# SH2-CONTROLS.net
KiCad netlist of a schematic drawn in Altium Designer
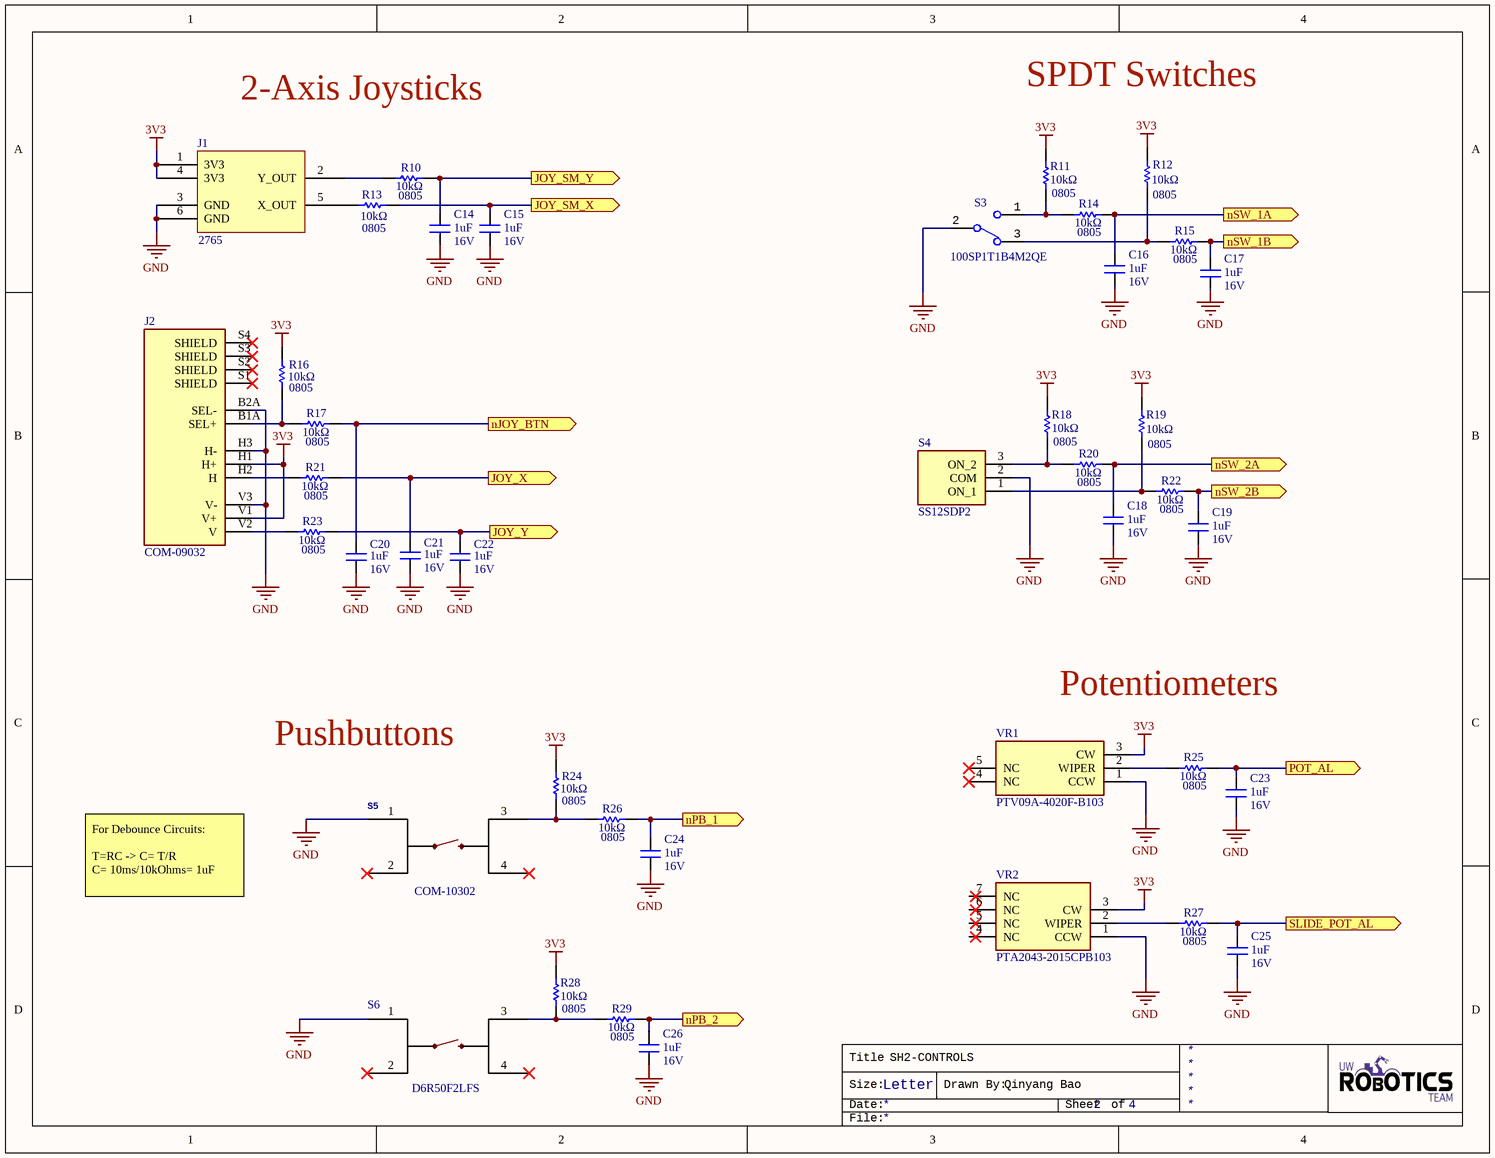
[diagram p0: SH2-CONTROLS.SchDoc]

(export (version "E")
  (design (tool "Eeschema 10.0.6"))
  (components
    (comp (ref "C14")
      (value "1uF")
      (footprint "CAPC2012X140N")
      (description "CAP CER 1UF 16V X7R 0805")
      (fields
        (field (name "TOLERANCE") "10%")
        (field (name "VOLTAGE RATING") "16V")
        (field (name "Comment") "CAP_1uF_16V_0805")
      )
      (libsource (lib "UWRT_Schematic_Library_2020") (part "CAP_1uF_16V_0805"))
    )
    (comp (ref "C15")
      (value "1uF")
      (footprint "CAPC2012X140N")
      (description "CAP CER 1UF 16V X7R 0805")
      (fields
        (field (name "TOLERANCE") "10%")
        (field (name "VOLTAGE RATING") "16V")
        (field (name "Comment") "CAP_1uF_16V_0805")
      )
      (libsource (lib "UWRT_Schematic_Library_2020") (part "CAP_1uF_16V_0805"))
    )
    (comp (ref "C16")
      (value "1uF")
      (footprint "CAPC2012X140N")
      (description "CAP CER 1UF 16V X7R 0805")
      (fields
        (field (name "TOLERANCE") "10%")
        (field (name "VOLTAGE RATING") "16V")
        (field (name "Comment") "CAP_1uF_16V_0805")
      )
      (libsource (lib "UWRT_Schematic_Library_2020") (part "CAP_1uF_16V_0805"))
    )
    (comp (ref "C17")
      (value "1uF")
      (footprint "CAPC2012X140N")
      (description "CAP CER 1UF 16V X7R 0805")
      (fields
        (field (name "TOLERANCE") "10%")
        (field (name "VOLTAGE RATING") "16V")
        (field (name "Comment") "CAP_1uF_16V_0805")
      )
      (libsource (lib "UWRT_Schematic_Library_2020") (part "CAP_1uF_16V_0805"))
    )
    (comp (ref "C18")
      (value "1uF")
      (footprint "CAPC2012X140N")
      (description "CAP CER 1UF 16V X7R 0805")
      (fields
        (field (name "TOLERANCE") "10%")
        (field (name "VOLTAGE RATING") "16V")
        (field (name "Comment") "CAP_1uF_16V_0805")
      )
      (libsource (lib "UWRT_Schematic_Library_2020") (part "CAP_1uF_16V_0805"))
    )
    (comp (ref "C19")
      (value "1uF")
      (footprint "CAPC2012X140N")
      (description "CAP CER 1UF 16V X7R 0805")
      (fields
        (field (name "TOLERANCE") "10%")
        (field (name "VOLTAGE RATING") "16V")
        (field (name "Comment") "CAP_1uF_16V_0805")
      )
      (libsource (lib "UWRT_Schematic_Library_2020") (part "CAP_1uF_16V_0805"))
    )
    (comp (ref "C20")
      (value "1uF")
      (footprint "CAPC2012X140N")
      (description "CAP CER 1UF 16V X7R 0805")
      (fields
        (field (name "TOLERANCE") "10%")
        (field (name "VOLTAGE RATING") "16V")
        (field (name "Comment") "CAP_1uF_16V_0805")
      )
      (libsource (lib "UWRT_Schematic_Library_2020") (part "CAP_1uF_16V_0805"))
    )
    (comp (ref "C21")
      (value "1uF")
      (footprint "CAPC2012X140N")
      (description "CAP CER 1UF 16V X7R 0805")
      (fields
        (field (name "TOLERANCE") "10%")
        (field (name "VOLTAGE RATING") "16V")
        (field (name "Comment") "CAP_1uF_16V_0805")
      )
      (libsource (lib "UWRT_Schematic_Library_2020") (part "CAP_1uF_16V_0805"))
    )
    (comp (ref "C22")
      (value "1uF")
      (footprint "CAPC2012X140N")
      (description "CAP CER 1UF 16V X7R 0805")
      (fields
        (field (name "TOLERANCE") "10%")
        (field (name "VOLTAGE RATING") "16V")
        (field (name "Comment") "CAP_1uF_16V_0805")
      )
      (libsource (lib "UWRT_Schematic_Library_2020") (part "CAP_1uF_16V_0805"))
    )
    (comp (ref "C23")
      (value "1uF")
      (footprint "CAPC2012X140N")
      (description "CAP CER 1UF 16V X7R 0805")
      (fields
        (field (name "TOLERANCE") "10%")
        (field (name "VOLTAGE RATING") "16V")
        (field (name "Comment") "CAP_1uF_16V_0805")
      )
      (libsource (lib "UWRT_Schematic_Library_2020") (part "CAP_1uF_16V_0805"))
    )
    (comp (ref "C24")
      (value "1uF")
      (footprint "CAPC2012X140N")
      (description "CAP CER 1UF 16V X7R 0805")
      (fields
        (field (name "TOLERANCE") "10%")
        (field (name "VOLTAGE RATING") "16V")
        (field (name "Comment") "CAP_1uF_16V_0805")
      )
      (libsource (lib "UWRT_Schematic_Library_2020") (part "CAP_1uF_16V_0805"))
    )
    (comp (ref "C25")
      (value "1uF")
      (footprint "CAPC2012X140N")
      (description "CAP CER 1UF 16V X7R 0805")
      (fields
        (field (name "TOLERANCE") "10%")
        (field (name "VOLTAGE RATING") "16V")
        (field (name "Comment") "CAP_1uF_16V_0805")
      )
      (libsource (lib "UWRT_Schematic_Library_2020") (part "CAP_1uF_16V_0805"))
    )
    (comp (ref "C26")
      (value "1uF")
      (footprint "CAPC2012X140N")
      (description "CAP CER 1UF 16V X7R 0805")
      (fields
        (field (name "TOLERANCE") "10%")
        (field (name "VOLTAGE RATING") "16V")
        (field (name "Comment") "CAP_1uF_16V_0805")
      )
      (libsource (lib "UWRT_Schematic_Library_2020") (part "CAP_1uF_16V_0805"))
    )
    (comp (ref "J1")
      (value "2_AXIS_JOYSTICK_SMALL")
      (footprint "2_AXIS_JOY_SMALL")
      (description "JOYSTICK 10K OHM 2 AXIS TH")
      (fields (field (name "MANUFACTURER PART NUMBER 1") "2765"))
      (libsource (lib "UWRT_Schematic_Library_2020") (part "2_AXIS_JOYSTICK_SMALL"))
    )
    (comp (ref "J2")
      (value "2_AXIS_JOYSTICK")
      (footprint "2_AXIS_JOY")
      (description "JOYSTICK 10K OHM 2 AXIS TH")
      (fields (field (name "MANUFACTURER PART NUMBER 1") "COM-09032"))
      (libsource (lib "UWRT_Schematic_Library_2020") (part "2_AXIS_JOYSTICK"))
    )
    (comp (ref "R10")
      (value "10kΩ")
      (footprint "RESC2012X60N")
      (description "RES SMD 10K OHM 1% 1/8W 0805")
      (fields
        (field (name "CASE CODE (IMPERIAL)") "0805")
        (field (name "TOLERANCE") "1%")
        (field (name "Comment") "RES_10kΩ_0805")
      )
      (libsource (lib "UWRT_Schematic_Library_2020") (part "RES_10kΩ_0805"))
    )
    (comp (ref "R11")
      (value "10kΩ")
      (footprint "RESC2012X60N")
      (description "RES SMD 10K OHM 1% 1/8W 0805")
      (fields
        (field (name "TOLERANCE") "1%")
        (field (name "CASE CODE (IMPERIAL)") "0805")
        (field (name "Comment") "RES_10kΩ_0805")
      )
      (libsource (lib "UWRT_Schematic_Library_2020") (part "RES_10kΩ_0805"))
    )
    (comp (ref "R12")
      (value "10kΩ")
      (footprint "RESC2012X60N")
      (description "RES SMD 10K OHM 1% 1/8W 0805")
      (fields
        (field (name "TOLERANCE") "1%")
        (field (name "CASE CODE (IMPERIAL)") "0805")
        (field (name "Comment") "RES_10kΩ_0805")
      )
      (libsource (lib "UWRT_Schematic_Library_2020") (part "RES_10kΩ_0805"))
    )
    (comp (ref "R13")
      (value "10kΩ")
      (footprint "RESC2012X60N")
      (description "RES SMD 10K OHM 1% 1/8W 0805")
      (fields
        (field (name "CASE CODE (IMPERIAL)") "0805")
        (field (name "TOLERANCE") "1%")
        (field (name "Comment") "RES_10kΩ_0805")
      )
      (libsource (lib "UWRT_Schematic_Library_2020") (part "RES_10kΩ_0805"))
    )
    (comp (ref "R14")
      (value "10kΩ")
      (footprint "RESC2012X60N")
      (description "RES SMD 10K OHM 1% 1/8W 0805")
      (fields
        (field (name "CASE CODE (IMPERIAL)") "0805")
        (field (name "TOLERANCE") "1%")
        (field (name "Comment") "RES_10kΩ_0805")
      )
      (libsource (lib "UWRT_Schematic_Library_2020") (part "RES_10kΩ_0805"))
    )
    (comp (ref "R15")
      (value "10kΩ")
      (footprint "RESC2012X60N")
      (description "RES SMD 10K OHM 1% 1/8W 0805")
      (fields
        (field (name "CASE CODE (IMPERIAL)") "0805")
        (field (name "TOLERANCE") "1%")
        (field (name "Comment") "RES_10kΩ_0805")
      )
      (libsource (lib "UWRT_Schematic_Library_2020") (part "RES_10kΩ_0805"))
    )
    (comp (ref "R16")
      (value "10kΩ")
      (footprint "RESC2012X60N")
      (description "RES SMD 10K OHM 1% 1/8W 0805")
      (fields
        (field (name "TOLERANCE") "1%")
        (field (name "CASE CODE (IMPERIAL)") "0805")
        (field (name "Comment") "RES_10kΩ_0805")
      )
      (libsource (lib "UWRT_Schematic_Library_2020") (part "RES_10kΩ_0805"))
    )
    (comp (ref "R17")
      (value "10kΩ")
      (footprint "RESC2012X60N")
      (description "RES SMD 10K OHM 1% 1/8W 0805")
      (fields
        (field (name "CASE CODE (IMPERIAL)") "0805")
        (field (name "TOLERANCE") "1%")
        (field (name "Comment") "RES_10kΩ_0805")
      )
      (libsource (lib "UWRT_Schematic_Library_2020") (part "RES_10kΩ_0805"))
    )
    (comp (ref "R18")
      (value "10kΩ")
      (footprint "RESC2012X60N")
      (description "RES SMD 10K OHM 1% 1/8W 0805")
      (fields
        (field (name "TOLERANCE") "1%")
        (field (name "CASE CODE (IMPERIAL)") "0805")
        (field (name "Comment") "RES_10kΩ_0805")
      )
      (libsource (lib "UWRT_Schematic_Library_2020") (part "RES_10kΩ_0805"))
    )
    (comp (ref "R19")
      (value "10kΩ")
      (footprint "RESC2012X60N")
      (description "RES SMD 10K OHM 1% 1/8W 0805")
      (fields
        (field (name "TOLERANCE") "1%")
        (field (name "CASE CODE (IMPERIAL)") "0805")
        (field (name "Comment") "RES_10kΩ_0805")
      )
      (libsource (lib "UWRT_Schematic_Library_2020") (part "RES_10kΩ_0805"))
    )
    (comp (ref "R20")
      (value "10kΩ")
      (footprint "RESC2012X60N")
      (description "RES SMD 10K OHM 1% 1/8W 0805")
      (fields
        (field (name "CASE CODE (IMPERIAL)") "0805")
        (field (name "TOLERANCE") "1%")
        (field (name "Comment") "RES_10kΩ_0805")
      )
      (libsource (lib "UWRT_Schematic_Library_2020") (part "RES_10kΩ_0805"))
    )
    (comp (ref "R21")
      (value "10kΩ")
      (footprint "RESC2012X60N")
      (description "RES SMD 10K OHM 1% 1/8W 0805")
      (fields
        (field (name "CASE CODE (IMPERIAL)") "0805")
        (field (name "TOLERANCE") "1%")
        (field (name "Comment") "RES_10kΩ_0805")
      )
      (libsource (lib "UWRT_Schematic_Library_2020") (part "RES_10kΩ_0805"))
    )
    (comp (ref "R22")
      (value "10kΩ")
      (footprint "RESC2012X60N")
      (description "RES SMD 10K OHM 1% 1/8W 0805")
      (fields
        (field (name "CASE CODE (IMPERIAL)") "0805")
        (field (name "TOLERANCE") "1%")
        (field (name "Comment") "RES_10kΩ_0805")
      )
      (libsource (lib "UWRT_Schematic_Library_2020") (part "RES_10kΩ_0805"))
    )
    (comp (ref "R23")
      (value "10kΩ")
      (footprint "RESC2012X60N")
      (description "RES SMD 10K OHM 1% 1/8W 0805")
      (fields
        (field (name "CASE CODE (IMPERIAL)") "0805")
        (field (name "TOLERANCE") "1%")
        (field (name "Comment") "RES_10kΩ_0805")
      )
      (libsource (lib "UWRT_Schematic_Library_2020") (part "RES_10kΩ_0805"))
    )
    (comp (ref "R24")
      (value "10kΩ")
      (footprint "RESC2012X60N")
      (description "RES SMD 10K OHM 1% 1/8W 0805")
      (fields
        (field (name "TOLERANCE") "1%")
        (field (name "CASE CODE (IMPERIAL)") "0805")
        (field (name "Comment") "RES_10kΩ_0805")
      )
      (libsource (lib "UWRT_Schematic_Library_2020") (part "RES_10kΩ_0805"))
    )
    (comp (ref "R25")
      (value "10kΩ")
      (footprint "RESC2012X60N")
      (description "RES SMD 10K OHM 1% 1/8W 0805")
      (fields
        (field (name "CASE CODE (IMPERIAL)") "0805")
        (field (name "TOLERANCE") "1%")
        (field (name "Comment") "RES_10kΩ_0805")
      )
      (libsource (lib "UWRT_Schematic_Library_2020") (part "RES_10kΩ_0805"))
    )
    (comp (ref "R26")
      (value "10kΩ")
      (footprint "RESC2012X60N")
      (description "RES SMD 10K OHM 1% 1/8W 0805")
      (fields
        (field (name "CASE CODE (IMPERIAL)") "0805")
        (field (name "TOLERANCE") "1%")
        (field (name "Comment") "RES_10kΩ_0805")
      )
      (libsource (lib "UWRT_Schematic_Library_2020") (part "RES_10kΩ_0805"))
    )
    (comp (ref "R27")
      (value "10kΩ")
      (footprint "RESC2012X60N")
      (description "RES SMD 10K OHM 1% 1/8W 0805")
      (fields
        (field (name "CASE CODE (IMPERIAL)") "0805")
        (field (name "TOLERANCE") "1%")
        (field (name "Comment") "RES_10kΩ_0805")
      )
      (libsource (lib "UWRT_Schematic_Library_2020") (part "RES_10kΩ_0805"))
    )
    (comp (ref "R28")
      (value "10kΩ")
      (footprint "RESC2012X60N")
      (description "RES SMD 10K OHM 1% 1/8W 0805")
      (fields
        (field (name "TOLERANCE") "1%")
        (field (name "CASE CODE (IMPERIAL)") "0805")
        (field (name "Comment") "RES_10kΩ_0805")
      )
      (libsource (lib "UWRT_Schematic_Library_2020") (part "RES_10kΩ_0805"))
    )
    (comp (ref "R29")
      (value "10kΩ")
      (footprint "RESC2012X60N")
      (description "RES SMD 10K OHM 1% 1/8W 0805")
      (fields
        (field (name "CASE CODE (IMPERIAL)") "0805")
        (field (name "TOLERANCE") "1%")
        (field (name "Comment") "RES_10kΩ_0805")
      )
      (libsource (lib "UWRT_Schematic_Library_2020") (part "RES_10kΩ_0805"))
    )
    (comp (ref "S3")
      (value "SW_SPDT")
      (footprint "100SP1T1B4M2QE")
      (description "SWITCH TOGGLE SPDT 5A 120V")
      (fields (field (name "MANUFACTURER PART NUMBER 1") "100SP1T1B4M2QE"))
      (libsource (lib "UWRT_Schematic_Library_2020") (part "SW_SPDT"))
    )
    (comp (ref "S4")
      (value "SW_SPDT_SMALL")
      (footprint "SS12SDP2")
      (description "SWITCH SLIDE SPDT 100MA 30V")
      (fields (field (name "MANUFACTURER PART NUMBER 1") "SS12SDP2"))
      (libsource (lib "UWRT_Schematic_Library_2020") (part "SW_SPDT_SMALL"))
    )
    (comp (ref "S5")
      (value "Pushbutton")
      (footprint "TACTILE_SWITCH_PTH_12MM")
      (description "Momentary Switch (Pushbutton) - SPST")
      (fields (field (name "MANUFACTURER PART NUMBER 1") "COM-10302"))
      (libsource (lib "UWRT_Schematic_Library_2020") (part "MOMENTARY_SWITCH_TH"))
    )
    (comp (ref "S6")
      (value "MOMENTARY_SWITCH_D6R")
      (footprint "D6R")
      (description "SWITCH PUSH SPST-NO 0.1A 32V")
      (fields (field (name "MANUFACTURER PART NUMBER 1") "D6R50F2LFS"))
      (libsource (lib "UWRT_Schematic_Library_2020") (part "MOMENTARY_SWITCH_D6R"))
    )
    (comp (ref "VR1")
      (value "POT_10K")
      (footprint "PTV09A4020FB103")
      (description "POT 10K OHM 1/20W CARBON LINEAR")
      (fields
        (field (name "MANUFACTURER PART NUMBER 1") "PTV09A-4020F-B103")
        (field (name "TOLERANCE") "20%")
      )
      (libsource (lib "UWRT_Schematic_Library_2020") (part "POT_10K"))
    )
    (comp (ref "VR2")
      (value "POT_10K_SLIDE")
      (footprint "PTA20432015CPB103")
      (description "SLIDE POT 10K OHM 0.1W TOP 20MM")
      (fields
        (field (name "MANUFACTURER PART NUMBER 1") "PTA2043-2015CPB103")
        (field (name "TOLERANCE") "20%")
      )
      (libsource (lib "UWRT_Schematic_Library_2020") (part "POT_10K_SLIDE"))
    )
  )
  (nets
    (net (code "1") (name "/JOY_SM_X") (class "Default")
      (node (ref "C15") (pin "2") (pinfunction "2_2") (pintype "passive"))
      (node (ref "R13") (pin "2") (pinfunction "2_2") (pintype "passive"))
    )
    (net (code "2") (name "/JOY_SM_Y") (class "Default")
      (node (ref "C14") (pin "2") (pinfunction "2_2") (pintype "passive"))
      (node (ref "R10") (pin "2") (pinfunction "2_2") (pintype "passive"))
    )
    (net (code "3") (name "/JOY_X") (class "Default")
      (node (ref "C21") (pin "2") (pinfunction "2_2") (pintype "passive"))
      (node (ref "R21") (pin "2") (pinfunction "2_2") (pintype "passive"))
    )
    (net (code "4") (name "/JOY_Y") (class "Default")
      (node (ref "C22") (pin "2") (pinfunction "2_2") (pintype "passive"))
      (node (ref "R23") (pin "2") (pinfunction "2_2") (pintype "passive"))
    )
    (net (code "5") (name "/POT_AL") (class "Default")
      (node (ref "C23") (pin "2") (pinfunction "2_2") (pintype "passive"))
      (node (ref "R25") (pin "2") (pinfunction "2_2") (pintype "passive"))
    )
    (net (code "6") (name "/SLIDE_POT_AL") (class "Default")
      (node (ref "C25") (pin "2") (pinfunction "2_2") (pintype "passive"))
      (node (ref "R27") (pin "2") (pinfunction "2_2") (pintype "passive"))
    )
    (net (code "7") (name "/nJOY_BTN") (class "Default")
      (node (ref "C20") (pin "2") (pinfunction "2_2") (pintype "passive"))
      (node (ref "R17") (pin "2") (pinfunction "2_2") (pintype "passive"))
    )
    (net (code "8") (name "/nPB_1") (class "Default")
      (node (ref "C24") (pin "2") (pinfunction "2_2") (pintype "passive"))
      (node (ref "R26") (pin "2") (pinfunction "2_2") (pintype "passive"))
    )
    (net (code "9") (name "/nPB_2") (class "Default")
      (node (ref "C26") (pin "2") (pinfunction "2_2") (pintype "passive"))
      (node (ref "R29") (pin "2") (pinfunction "2_2") (pintype "passive"))
    )
    (net (code "10") (name "/nSW_1A") (class "Default")
      (node (ref "C16") (pin "2") (pinfunction "2_2") (pintype "passive"))
      (node (ref "R14") (pin "2") (pinfunction "2_2") (pintype "passive"))
    )
    (net (code "11") (name "/nSW_1B") (class "Default")
      (node (ref "C17") (pin "2") (pinfunction "2_2") (pintype "passive"))
      (node (ref "R15") (pin "2") (pinfunction "2_2") (pintype "passive"))
    )
    (net (code "12") (name "/nSW_2A") (class "Default")
      (node (ref "C18") (pin "2") (pinfunction "2_2") (pintype "passive"))
      (node (ref "R20") (pin "2") (pinfunction "2_2") (pintype "passive"))
    )
    (net (code "13") (name "/nSW_2B") (class "Default")
      (node (ref "C19") (pin "2") (pinfunction "2_2") (pintype "passive"))
      (node (ref "R22") (pin "2") (pinfunction "2_2") (pintype "passive"))
    )
    (net (code "14") (name "3V3") (class "Default")
      (node (ref "J1") (pin "1") (pinfunction "3V3_1") (pintype "passive"))
      (node (ref "J1") (pin "4") (pinfunction "3V3_4") (pintype "passive"))
      (node (ref "J2") (pin "H1") (pinfunction "H+_H1") (pintype "passive"))
      (node (ref "J2") (pin "V1") (pinfunction "V+_V1") (pintype "passive"))
      (node (ref "R11") (pin "1") (pinfunction "1_1") (pintype "passive"))
      (node (ref "R12") (pin "1") (pinfunction "1_1") (pintype "passive"))
      (node (ref "R16") (pin "1") (pinfunction "1_1") (pintype "passive"))
      (node (ref "R18") (pin "1") (pinfunction "1_1") (pintype "passive"))
      (node (ref "R19") (pin "1") (pinfunction "1_1") (pintype "passive"))
      (node (ref "R24") (pin "1") (pinfunction "1_1") (pintype "passive"))
      (node (ref "R28") (pin "1") (pinfunction "1_1") (pintype "passive"))
      (node (ref "VR1") (pin "3") (pinfunction "CW_3") (pintype "passive"))
      (node (ref "VR2") (pin "3") (pinfunction "CW_3") (pintype "passive"))
    )
    (net (code "15") (name "GND") (class "Default")
      (node (ref "C14") (pin "1") (pinfunction "1_1") (pintype "passive"))
      (node (ref "C15") (pin "1") (pinfunction "1_1") (pintype "passive"))
      (node (ref "C16") (pin "1") (pinfunction "1_1") (pintype "passive"))
      (node (ref "C17") (pin "1") (pinfunction "1_1") (pintype "passive"))
      (node (ref "C18") (pin "1") (pinfunction "1_1") (pintype "passive"))
      (node (ref "C19") (pin "1") (pinfunction "1_1") (pintype "passive"))
      (node (ref "C20") (pin "1") (pinfunction "1_1") (pintype "passive"))
      (node (ref "C21") (pin "1") (pinfunction "1_1") (pintype "passive"))
      (node (ref "C22") (pin "1") (pinfunction "1_1") (pintype "passive"))
      (node (ref "C23") (pin "1") (pinfunction "1_1") (pintype "passive"))
      (node (ref "C24") (pin "1") (pinfunction "1_1") (pintype "passive"))
      (node (ref "C25") (pin "1") (pinfunction "1_1") (pintype "passive"))
      (node (ref "C26") (pin "1") (pinfunction "1_1") (pintype "passive"))
      (node (ref "J1") (pin "3") (pinfunction "GND_3") (pintype "passive"))
      (node (ref "J1") (pin "6") (pinfunction "GND_6") (pintype "passive"))
      (node (ref "J2") (pin "B2A") (pinfunction "SEL-_B2A") (pintype "passive"))
      (node (ref "J2") (pin "H3") (pinfunction "H-_H3") (pintype "passive"))
      (node (ref "J2") (pin "V3") (pinfunction "V-_V3") (pintype "passive"))
      (node (ref "S3") (pin "2") (pinfunction "2_2") (pintype "passive"))
      (node (ref "S4") (pin "2") (pinfunction "COM_2") (pintype "passive"))
      (node (ref "S5") (pin "1") (pinfunction "1_1") (pintype "passive"))
      (node (ref "S6") (pin "1") (pinfunction "1_1") (pintype "passive"))
      (node (ref "VR1") (pin "1") (pinfunction "CCW_1") (pintype "passive"))
      (node (ref "VR2") (pin "1") (pinfunction "CCW_1") (pintype "passive"))
    )
    (net (code "16") (name "Net-(J1-X_OUT)") (class "Default")
      (node (ref "J1") (pin "5") (pinfunction "X_OUT_5") (pintype "passive"))
      (node (ref "R13") (pin "1") (pinfunction "1_1") (pintype "passive"))
    )
    (net (code "17") (name "Net-(J1-Y_OUT)") (class "Default")
      (node (ref "J1") (pin "2") (pinfunction "Y_OUT_2") (pintype "passive"))
      (node (ref "R10") (pin "1") (pinfunction "1_1") (pintype "passive"))
    )
    (net (code "18") (name "Net-(J2-H)") (class "Default")
      (node (ref "J2") (pin "H2") (pinfunction "H_H2") (pintype "passive"))
      (node (ref "R21") (pin "1") (pinfunction "1_1") (pintype "passive"))
    )
    (net (code "19") (name "Net-(J2-SEL+)") (class "Default")
      (node (ref "J2") (pin "B1A") (pinfunction "SEL+_B1A") (pintype "passive"))
      (node (ref "R16") (pin "2") (pinfunction "2_2") (pintype "passive"))
      (node (ref "R17") (pin "1") (pinfunction "1_1") (pintype "passive"))
    )
    (net (code "20") (name "Net-(J2-V)") (class "Default")
      (node (ref "J2") (pin "V2") (pinfunction "V_V2") (pintype "passive"))
      (node (ref "R23") (pin "1") (pinfunction "1_1") (pintype "passive"))
    )
    (net (code "21") (name "Net-(R11-Pad2)") (class "Default")
      (node (ref "R11") (pin "2") (pinfunction "2_2") (pintype "passive"))
      (node (ref "R14") (pin "1") (pinfunction "1_1") (pintype "passive"))
      (node (ref "S3") (pin "1") (pinfunction "1_1") (pintype "passive"))
    )
    (net (code "22") (name "Net-(R12-Pad2)") (class "Default")
      (node (ref "R12") (pin "2") (pinfunction "2_2") (pintype "passive"))
      (node (ref "R15") (pin "1") (pinfunction "1_1") (pintype "passive"))
      (node (ref "S3") (pin "3") (pinfunction "3_3") (pintype "passive"))
    )
    (net (code "23") (name "Net-(R24-Pad2)") (class "Default")
      (node (ref "R24") (pin "2") (pinfunction "2_2") (pintype "passive"))
      (node (ref "R26") (pin "1") (pinfunction "1_1") (pintype "passive"))
      (node (ref "S5") (pin "3") (pinfunction "3_3") (pintype "passive"))
    )
    (net (code "24") (name "Net-(R28-Pad2)") (class "Default")
      (node (ref "R28") (pin "2") (pinfunction "2_2") (pintype "passive"))
      (node (ref "R29") (pin "1") (pinfunction "1_1") (pintype "passive"))
      (node (ref "S6") (pin "3") (pinfunction "3_3") (pintype "passive"))
    )
    (net (code "25") (name "Net-(S4-ON_1)") (class "Default")
      (node (ref "R19") (pin "2") (pinfunction "2_2") (pintype "passive"))
      (node (ref "R22") (pin "1") (pinfunction "1_1") (pintype "passive"))
      (node (ref "S4") (pin "1") (pinfunction "ON_1_1") (pintype "passive"))
    )
    (net (code "26") (name "Net-(S4-ON_2)") (class "Default")
      (node (ref "R18") (pin "2") (pinfunction "2_2") (pintype "passive"))
      (node (ref "R20") (pin "1") (pinfunction "1_1") (pintype "passive"))
      (node (ref "S4") (pin "3") (pinfunction "ON_2_3") (pintype "passive"))
    )
    (net (code "27") (name "Net-(VR1-WIPER)") (class "Default")
      (node (ref "R25") (pin "1") (pinfunction "1_1") (pintype "passive"))
      (node (ref "VR1") (pin "2") (pinfunction "WIPER_2") (pintype "passive"))
    )
    (net (code "28") (name "Net-(VR2-WIPER)") (class "Default")
      (node (ref "R27") (pin "1") (pinfunction "1_1") (pintype "passive"))
      (node (ref "VR2") (pin "2") (pinfunction "WIPER_2") (pintype "passive"))
    )
    (net (code "29") (name "unconnected-(J2-SHIELD-PadS1)") (class "Default")
      (node (ref "J2") (pin "S1") (pinfunction "SHIELD_S1") (pintype "passive+no_connect"))
    )
    (net (code "30") (name "unconnected-(J2-SHIELD-PadS2)") (class "Default")
      (node (ref "J2") (pin "S2") (pinfunction "SHIELD_S2") (pintype "passive+no_connect"))
    )
    (net (code "31") (name "unconnected-(J2-SHIELD-PadS3)") (class "Default")
      (node (ref "J2") (pin "S3") (pinfunction "SHIELD_S3") (pintype "passive+no_connect"))
    )
    (net (code "32") (name "unconnected-(J2-SHIELD-PadS4)") (class "Default")
      (node (ref "J2") (pin "S4") (pinfunction "SHIELD_S4") (pintype "passive+no_connect"))
    )
    (net (code "33") (name "unconnected-(S5-Pad2)") (class "Default")
      (node (ref "S5") (pin "2") (pinfunction "2_2") (pintype "passive+no_connect"))
    )
    (net (code "34") (name "unconnected-(S5-Pad4)") (class "Default")
      (node (ref "S5") (pin "4") (pinfunction "4_4") (pintype "passive+no_connect"))
    )
    (net (code "35") (name "unconnected-(S6-Pad2)") (class "Default")
      (node (ref "S6") (pin "2") (pinfunction "2_2") (pintype "passive+no_connect"))
    )
    (net (code "36") (name "unconnected-(S6-Pad4)") (class "Default")
      (node (ref "S6") (pin "4") (pinfunction "4_4") (pintype "passive+no_connect"))
    )
    (net (code "37") (name "unconnected-(VR1-NC-Pad4)") (class "Default")
      (node (ref "VR1") (pin "4") (pinfunction "NC_4") (pintype "passive+no_connect"))
    )
    (net (code "38") (name "unconnected-(VR1-NC-Pad5)") (class "Default")
      (node (ref "VR1") (pin "5") (pinfunction "NC_5") (pintype "passive+no_connect"))
    )
    (net (code "39") (name "unconnected-(VR2-NC-Pad4)") (class "Default")
      (node (ref "VR2") (pin "4") (pinfunction "NC_4") (pintype "passive"))
    )
    (net (code "40") (name "unconnected-(VR2-NC-Pad5)") (class "Default")
      (node (ref "VR2") (pin "5") (pinfunction "NC_5") (pintype "passive"))
    )
    (net (code "41") (name "unconnected-(VR2-NC-Pad6)") (class "Default")
      (node (ref "VR2") (pin "6") (pinfunction "NC_6") (pintype "passive"))
    )
    (net (code "42") (name "unconnected-(VR2-NC-Pad7)") (class "Default")
      (node (ref "VR2") (pin "7") (pinfunction "NC_7") (pintype "passive"))
    )
  )
)
